# 12V0_REG.net
KiCad netlist of a schematic drawn in Altium Designer
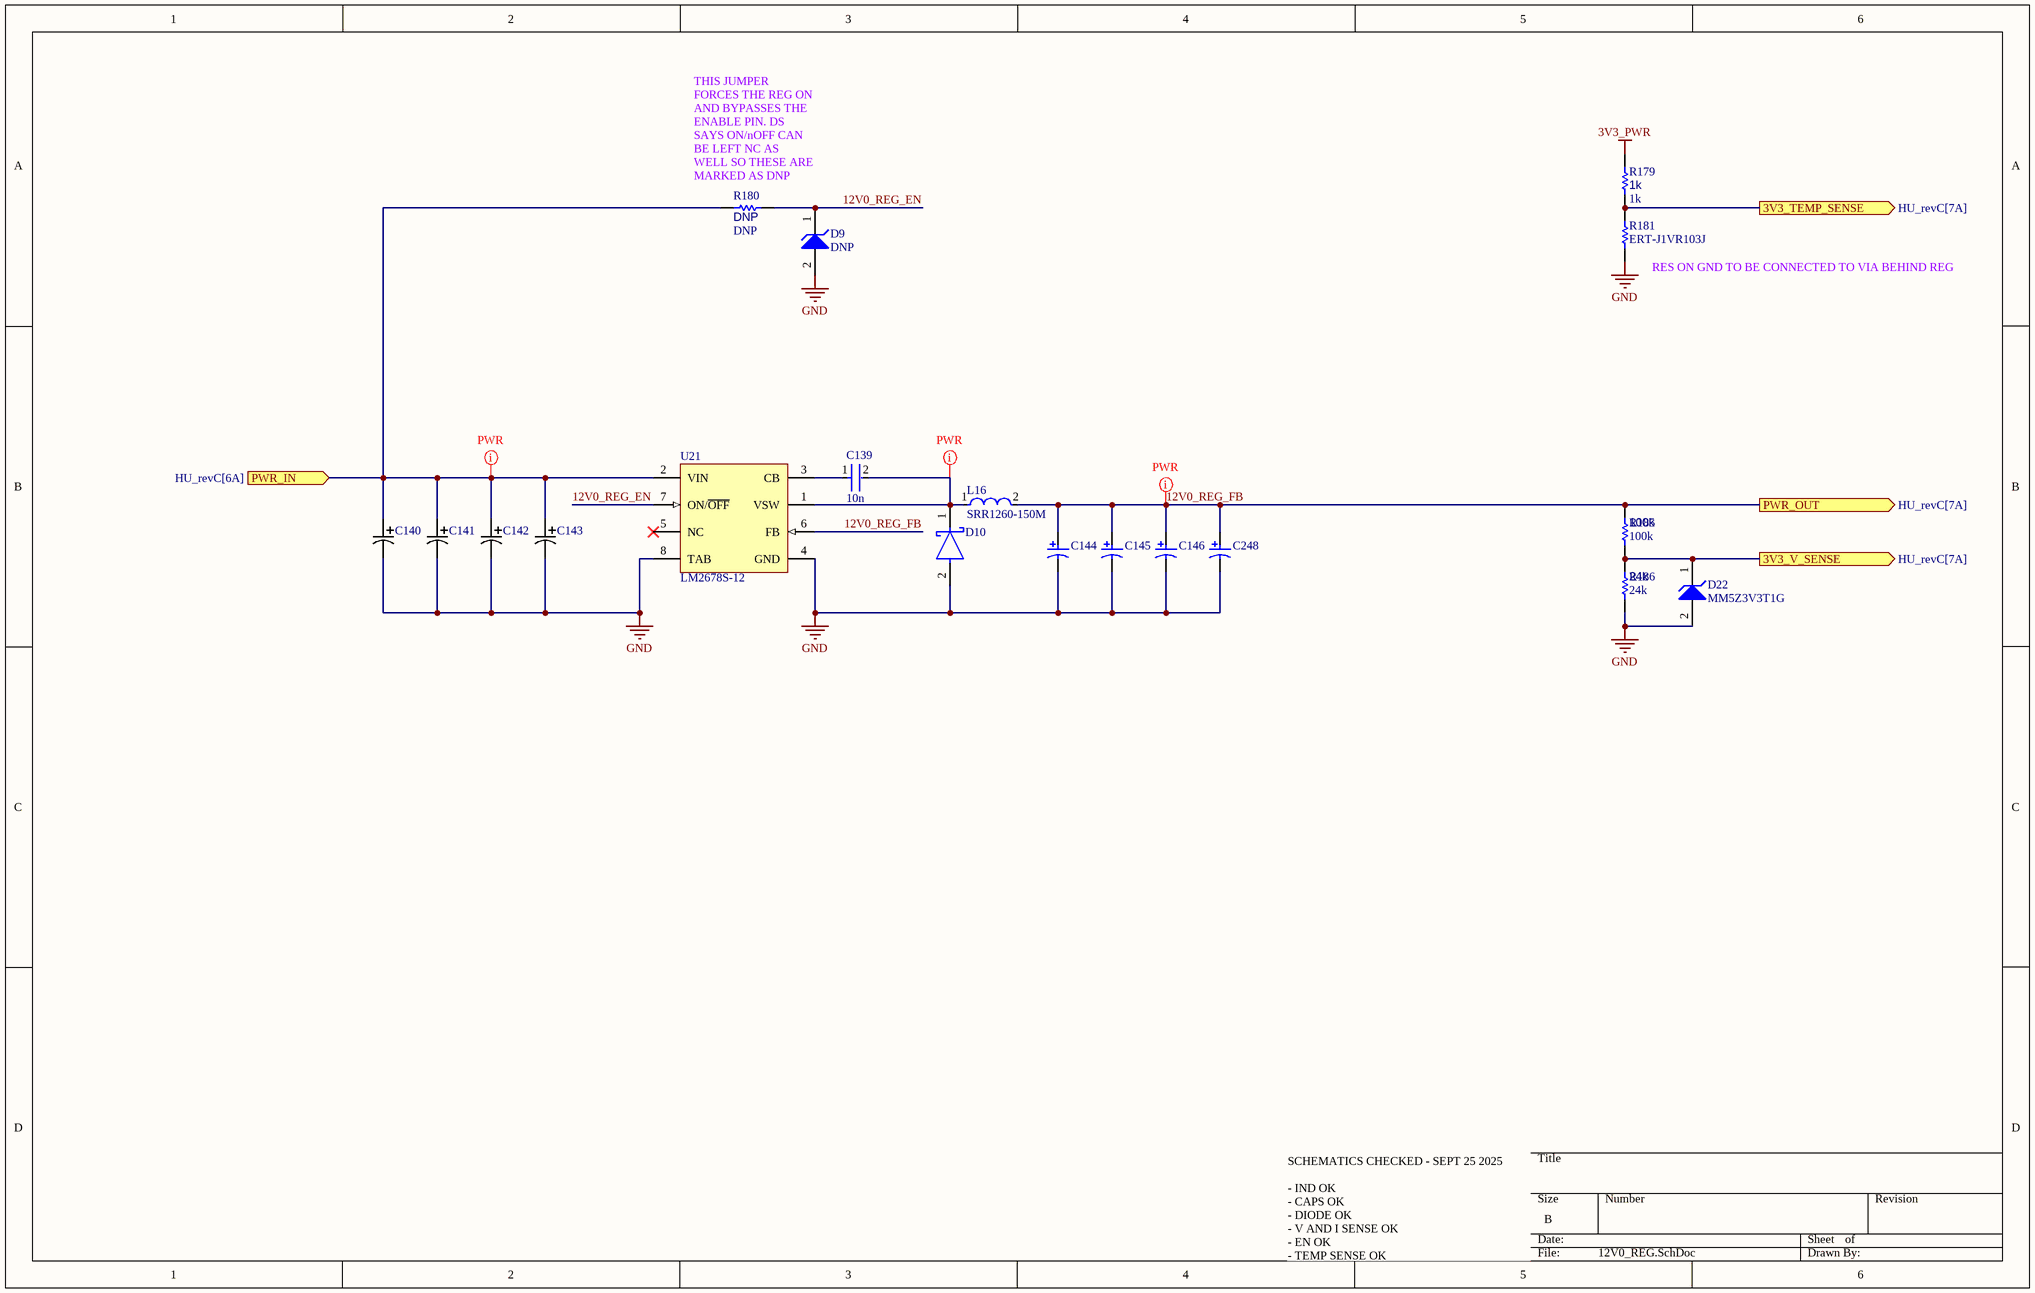
[diagram p0: 12V0_REG.SchDoc]

(export (version "E")
  (design (tool "Eeschema 10.0.6"))
  (components
    (comp (ref "C139")
      (value "10n")
      (footprint "FP-0402-L_1_0_0_05-W_0_5-IPC_A")
      (description "LARGE PADS, 0402 CAP, CHANGE COMMENT TO MATCH REAL P/N")
      (libsource (lib "Space Concordia") (part "b4654b650e69147ec39a6b967a45e02"))
    )
    (comp (ref "C140")
      (value "T495D106M035ATE260")
      (footprint "T495D106M035ATE260-Footprint-1")
      (fields (field (name "TOLERANCE") "20%"))
      (libsource (lib "Space Concordia") (part "T495D106M035ATE260"))
    )
    (comp (ref "C141")
      (value "T495D106M035ATE260")
      (footprint "T495D106M035ATE260-Footprint-1")
      (fields (field (name "TOLERANCE") "20%"))
      (libsource (lib "Space Concordia") (part "T495D106M035ATE260"))
    )
    (comp (ref "C142")
      (value "T495D106M035ATE260")
      (footprint "T495D106M035ATE260-Footprint-1")
      (fields (field (name "TOLERANCE") "20%"))
      (libsource (lib "Space Concordia") (part "T495D106M035ATE260"))
    )
    (comp (ref "C143")
      (value "T495D106M035ATE260")
      (footprint "T495D106M035ATE260-Footprint-1")
      (fields (field (name "TOLERANCE") "20%"))
      (libsource (lib "Space Concordia") (part "T495D106M035ATE260"))
    )
    (comp (ref "C144")
      (value "T495D686K020ATE150")
      (footprint "KEMT-T495-D_L")
      (description "T495D686K020ATE150 - diff p/n (68U 20V)")
      (fields (field (name "MANUFACTURER") "Kemet"))
      (libsource (lib "Altium Content Vault") (part "CAP-P-2"))
    )
    (comp (ref "C145")
      (value "T495D686K020ATE150")
      (footprint "KEMT-T495-D_L")
      (description "T495D686K020ATE150 - diff p/n (68U 20V)")
      (fields (field (name "MANUFACTURER") "Kemet"))
      (libsource (lib "Altium Content Vault") (part "CAP-P-2"))
    )
    (comp (ref "C146")
      (value "T495D686K020ATE150")
      (footprint "KEMT-T495-D_L")
      (description "T495D686K020ATE150 - diff p/n (68U 20V)")
      (fields (field (name "MANUFACTURER") "Kemet"))
      (libsource (lib "Altium Content Vault") (part "CAP-P-2"))
    )
    (comp (ref "C248")
      (value "T495D686K020ATE150")
      (footprint "KEMT-T495-D_L")
      (description "T495D686K020ATE150 - diff p/n (68U 20V)")
      (fields (field (name "MANUFACTURER") "Kemet"))
      (libsource (lib "Altium Content Vault") (part "CAP-P-2"))
    )
    (comp (ref "D9")
      (value "DNP")
      (footprint "ONSC-SOD-523-2-502-01_V")
      (description "Zener Voltage Regulator, 500 mW, 2-Pin SOD-523, Pb-Free, Tape and Reel")
      (fields (field (name "MANUFACTURER") "On Semiconductor") (field (name "PARTNUMBER") "MM5Z3V3T1G"))
      (libsource (lib "Altium Content Vault") (part "ONSC-K1A2-2"))
    )
    (comp (ref "D10")
      (value "B540C-13-F")
      (footprint "FP-SMC-MFG")
      (description "DIODE SCHOTTKY 40V 5A SMC")
      (fields
        (field (name "OCTOPART") "https://octopart.com/b540c-13-f-diodes+inc.-325873")
        (field (name "MANUFACTURER") "Diodes Inc.")
      )
      (libsource (lib "Altium Content Vault") (part "1d6ec82d83fb6aee721767c19dac4b9"))
    )
    (comp (ref "D22")
      (value "MM5Z3V3T1G")
      (footprint "ONSC-SOD-523-2-502-01_V")
      (description "Zener Voltage Regulator, 500 mW, 2-Pin SOD-523, Pb-Free, Tape and Reel")
      (fields (field (name "MANUFACTURER") "On Semiconductor"))
      (libsource (lib "Altium Content Vault") (part "ONSC-K1A2-2"))
    )
    (comp (ref "L16")
      (value "SRR1260-150M")
      (footprint "FP-SRR1260-MFG")
      (description "FIXED IND 15UH 5A 27 MOHM SMD")
      (fields (field (name "TOLERANCE") "20%"))
      (libsource (lib "Altium Content Vault") (part "725321dda6339637d4d059423bc1c3c"))
    )
    (comp (ref "R179")
      (value "1k")
      (footprint "R0603B")
      (description "Resistor")
      (fields (field (name "ALTIUM_VALUE") "1k"))
      (libsource (lib "Space Concordia") (part "Resistor"))
    )
    (comp (ref "R180")
      (value "DNP")
      (footprint "R0603B")
      (description "Resistor")
      (fields (field (name "ALTIUM_VALUE") "DNP"))
      (libsource (lib "Space Concordia") (part "Resistor"))
    )
    (comp (ref "R181")
      (value "ERT-J1VR103J")
      (footprint "RESC1608X90X30ML15T20")
      (fields (field (name "MANUFACTURER") "Panasonic"))
      (libsource (lib "Altium Content Vault") (part "RES"))
    )
    (comp (ref "R185")
      (value "100k")
      (footprint "R0603B")
      (description "Resistor")
      (fields (field (name "ALTIUM_VALUE") "100k"))
      (libsource (lib "Space Concordia") (part "Resistor"))
    )
    (comp (ref "R186")
      (value "24k")
      (footprint "R0603B")
      (description "Resistor")
      (fields (field (name "ALTIUM_VALUE") "24k"))
      (libsource (lib "Space Concordia") (part "Resistor"))
    )
    (comp (ref "U21")
      (value "LM2678S-12")
      (footprint "KTW0007B_L")
      (description "SIMPLE SWITCHER® High Efficiency 5A Step-Down Voltage Regulator, 7-pin TO-263")
      (fields (field (name "MANUFACTURER") "Texas Instruments"))
      (libsource (lib "Altium Content Vault") (part "PM-REG-LM2678S"))
    )
  )
  (nets
    (net (code "1") (name "/3V3_TEMP_SENSE") (class "Default")
      (node (ref "R179") (pin "2") (pinfunction "2_2") (pintype "passive"))
      (node (ref "R181") (pin "2") (pinfunction "2_2") (pintype "passive"))
    )
    (net (code "2") (name "/3V3_V_SENSE") (class "Default")
      (node (ref "D22") (pin "1") (pinfunction "K_1") (pintype "passive"))
      (node (ref "R185") (pin "1") (pinfunction "1_1") (pintype "passive"))
      (node (ref "R186") (pin "2") (pinfunction "2_2") (pintype "passive"))
    )
    (net (code "3") (name "/12V0_REG_EN") (class "Default")
      (node (ref "D9") (pin "1") (pinfunction "K_1") (pintype "passive"))
      (node (ref "R180") (pin "2") (pinfunction "2_2") (pintype "passive"))
      (node (ref "U21") (pin "7") (pinfunction "ON/~{OFF}_7") (pintype "input"))
    )
    (net (code "4") (name "/12V0_REG_FB") (class "Default")
      (node (ref "C144") (pin "1") (pinfunction "1_1") (pintype "passive"))
      (node (ref "C145") (pin "1") (pinfunction "1_1") (pintype "passive"))
      (node (ref "C146") (pin "1") (pinfunction "1_1") (pintype "passive"))
      (node (ref "C248") (pin "1") (pinfunction "1_1") (pintype "passive"))
      (node (ref "L16") (pin "2") (pinfunction "2_2") (pintype "passive"))
      (node (ref "R185") (pin "2") (pinfunction "2_2") (pintype "passive"))
      (node (ref "U21") (pin "6") (pinfunction "FB_6") (pintype "input"))
    )
    (net (code "5") (name "/PWR_IN") (class "Default")
      (node (ref "C140") (pin "1") (pinfunction "1_1") (pintype "passive"))
      (node (ref "C141") (pin "1") (pinfunction "1_1") (pintype "passive"))
      (node (ref "C142") (pin "1") (pinfunction "1_1") (pintype "passive"))
      (node (ref "C143") (pin "1") (pinfunction "1_1") (pintype "passive"))
      (node (ref "R180") (pin "1") (pinfunction "1_1") (pintype "passive"))
      (node (ref "U21") (pin "2") (pinfunction "VIN_2") (pintype "power_in"))
    )
    (net (code "6") (name "3V3_PWR") (class "Default")
      (node (ref "R179") (pin "1") (pinfunction "1_1") (pintype "passive"))
    )
    (net (code "7") (name "GND") (class "Default")
      (node (ref "C140") (pin "2") (pinfunction "2_2") (pintype "passive"))
      (node (ref "C141") (pin "2") (pinfunction "2_2") (pintype "passive"))
      (node (ref "C142") (pin "2") (pinfunction "2_2") (pintype "passive"))
      (node (ref "C143") (pin "2") (pinfunction "2_2") (pintype "passive"))
      (node (ref "C144") (pin "2") (pinfunction "2_2") (pintype "passive"))
      (node (ref "C145") (pin "2") (pinfunction "2_2") (pintype "passive"))
      (node (ref "C146") (pin "2") (pinfunction "2_2") (pintype "passive"))
      (node (ref "C248") (pin "2") (pinfunction "2_2") (pintype "passive"))
      (node (ref "D10") (pin "2") (pinfunction "A_2") (pintype "passive"))
      (node (ref "D22") (pin "2") (pinfunction "A_2") (pintype "passive"))
      (node (ref "D9") (pin "2") (pinfunction "A_2") (pintype "passive"))
      (node (ref "R181") (pin "1") (pinfunction "1_1") (pintype "passive"))
      (node (ref "R186") (pin "1") (pinfunction "1_1") (pintype "passive"))
      (node (ref "U21") (pin "4") (pinfunction "GND_4") (pintype "power_in"))
      (node (ref "U21") (pin "8") (pinfunction "TAB_8") (pintype "power_in"))
    )
    (net (code "8") (name "Net-(D10-C)") (class "Default")
      (node (ref "C139") (pin "2") (pinfunction "2_2") (pintype "passive"))
      (node (ref "D10") (pin "1") (pinfunction "C_1") (pintype "passive"))
      (node (ref "L16") (pin "1") (pinfunction "1_1") (pintype "passive"))
      (node (ref "U21") (pin "1") (pinfunction "VSW_1") (pintype "power_in"))
    )
    (net (code "9") (name "Net-(U21-CB)") (class "Default")
      (node (ref "C139") (pin "1") (pinfunction "1_1") (pintype "passive"))
      (node (ref "U21") (pin "3") (pinfunction "CB_3") (pintype "passive"))
    )
    (net (code "10") (name "unconnected-(U21-NC-Pad5)") (class "Default")
      (node (ref "U21") (pin "5") (pinfunction "NC_5") (pintype "passive+no_connect"))
    )
  )
)
